# clogic.net
KiCad netlist of a schematic drawn in EAGLE
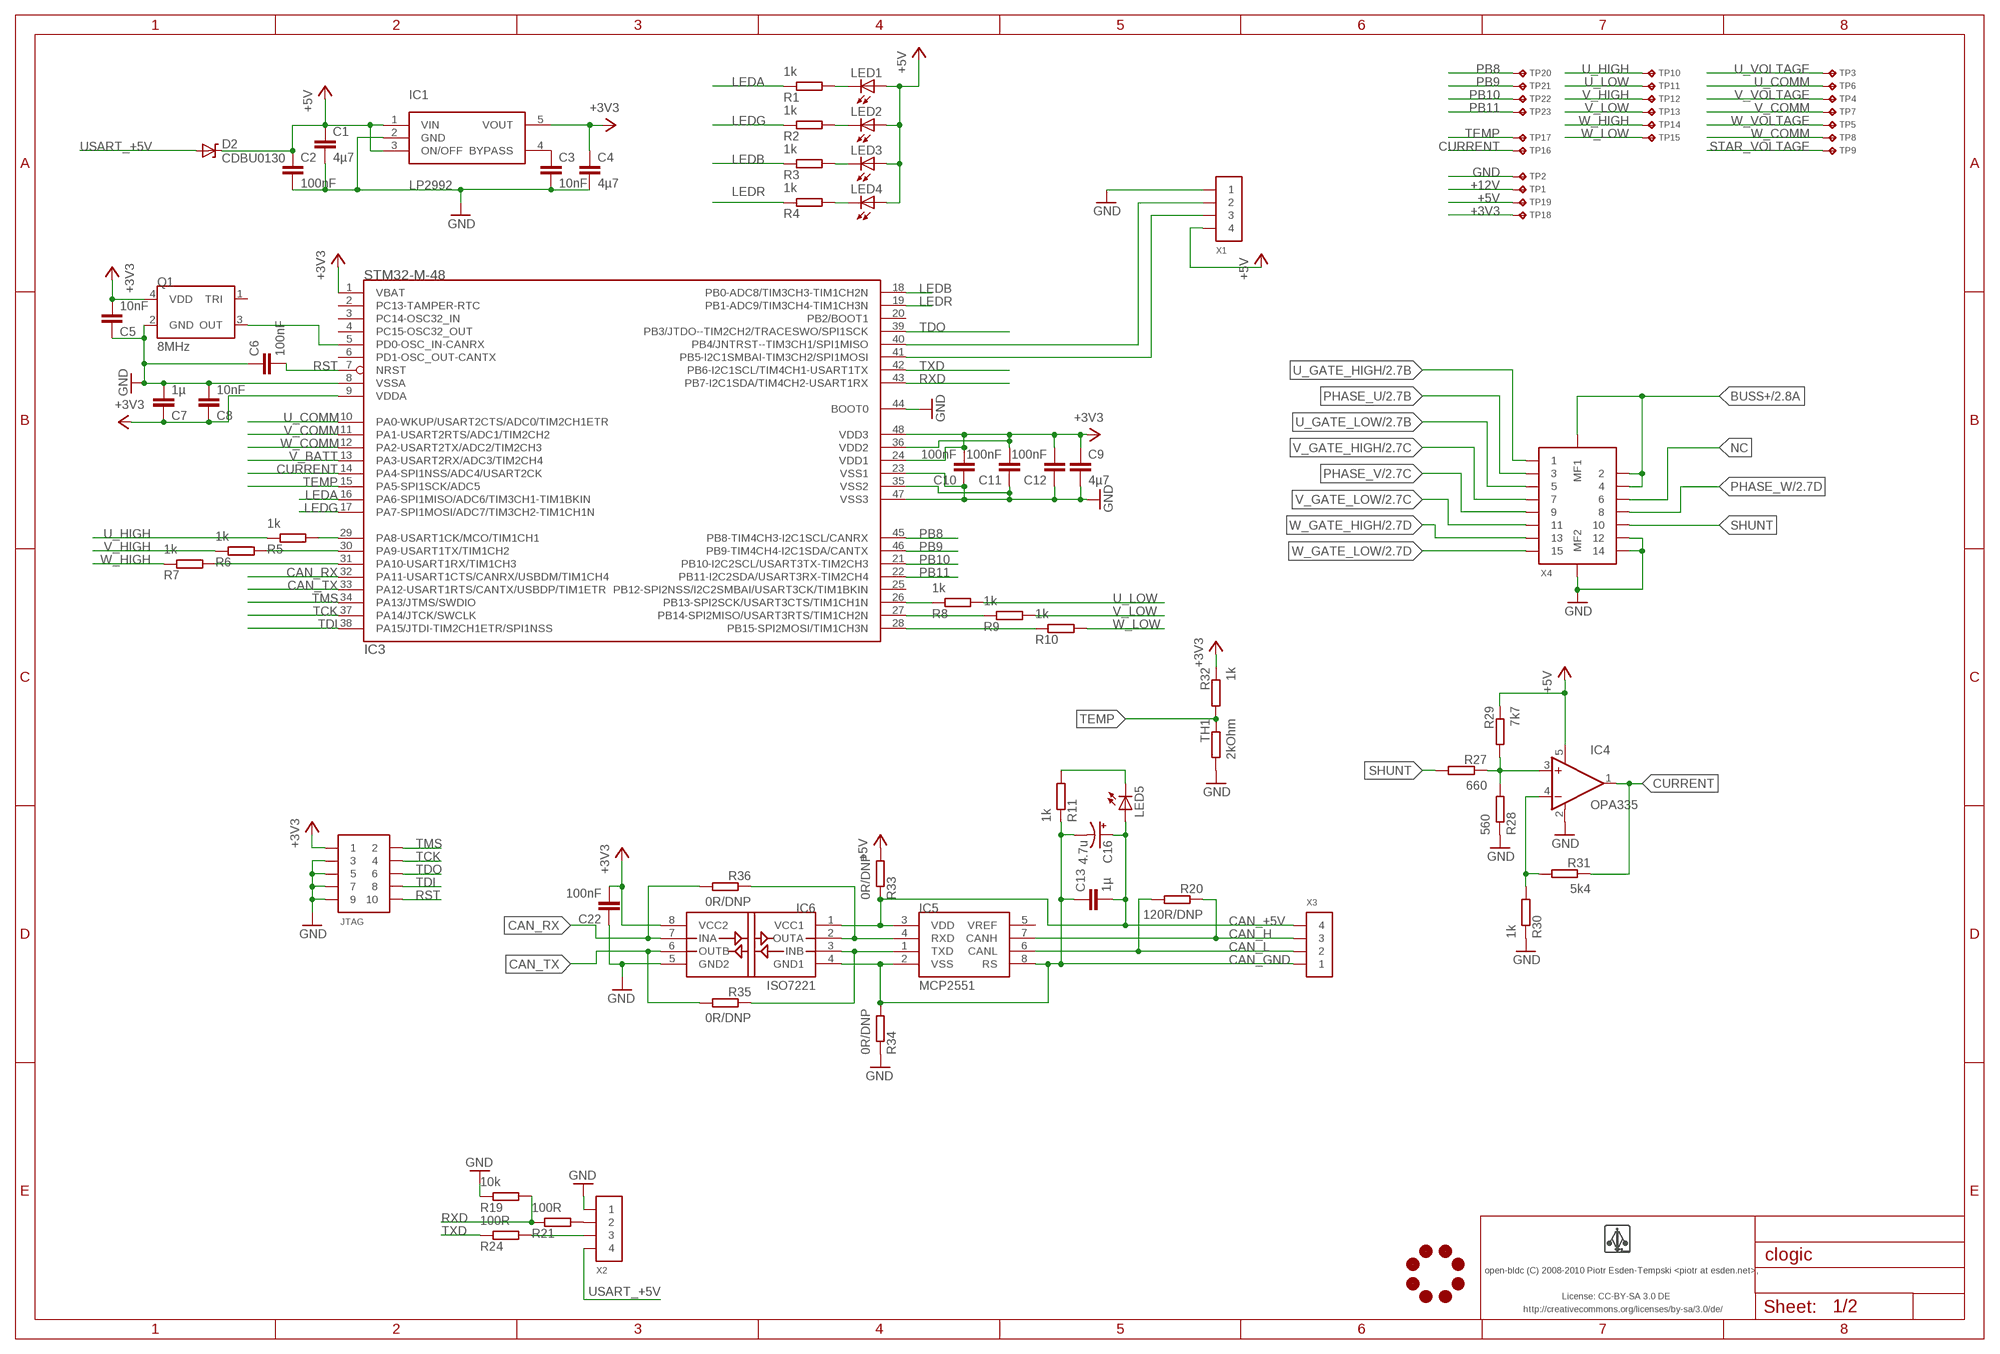
[diagram p0: schematic, sheet 1]
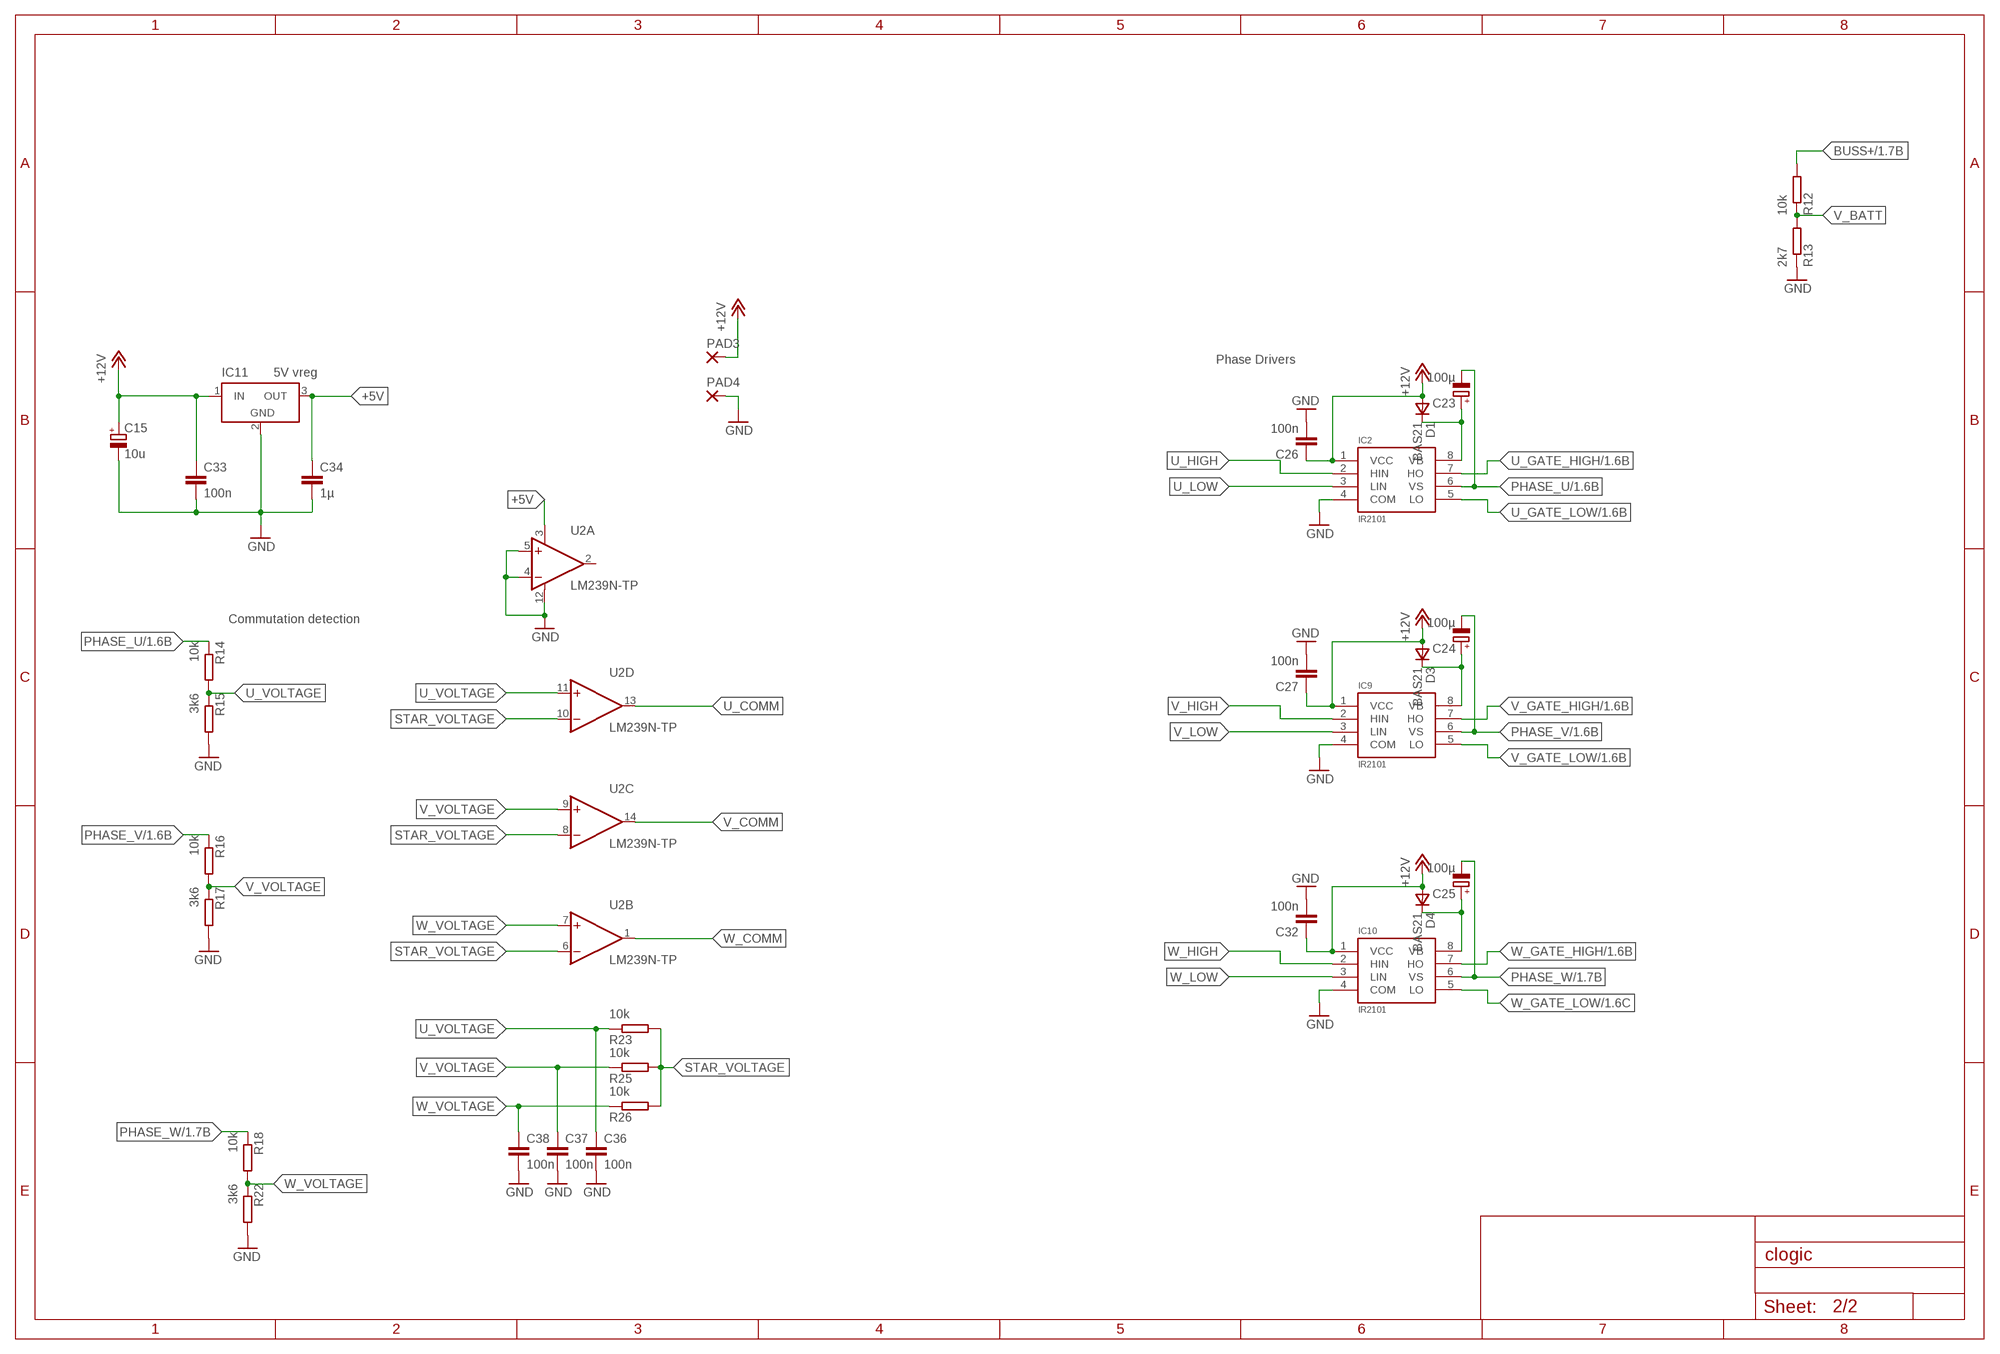
[diagram p1: schematic, sheet 2]

(export (version "E")
  (design (tool "Eeschema 10.0.6"))
  (components
    (comp (ref "C1")
      (value "4µ7")
      (footprint "eagle-import:0603-CAP")
      (libsource (lib "eagle-import") (part "CAPACITOR-0603"))
    )
    (comp (ref "C2")
      (value "100nF")
      (footprint "eagle-import:0603-CAP")
      (libsource (lib "eagle-import") (part "CAPACITOR-0603"))
    )
    (comp (ref "C3")
      (value "10nF")
      (footprint "eagle-import:0603-CAP")
      (libsource (lib "eagle-import") (part "CAPACITOR-0603"))
    )
    (comp (ref "C4")
      (value "4µ7")
      (footprint "eagle-import:0603-CAP")
      (libsource (lib "eagle-import") (part "CAPACITOR-0603"))
    )
    (comp (ref "C5")
      (value "10nF")
      (footprint "eagle-import:0603-CAP")
      (libsource (lib "eagle-import") (part "CAPACITOR-0603"))
    )
    (comp (ref "C6")
      (value "100nF")
      (footprint "eagle-import:0603-CAP")
      (libsource (lib "eagle-import") (part "CAPACITOR-0603"))
    )
    (comp (ref "C7")
      (value "1µ")
      (footprint "eagle-import:0603-CAP")
      (libsource (lib "eagle-import") (part "CAPACITOR-0603"))
    )
    (comp (ref "C8")
      (value "10nF")
      (footprint "eagle-import:0603-CAP")
      (libsource (lib "eagle-import") (part "CAPACITOR-0603"))
    )
    (comp (ref "C9")
      (value "4µ7")
      (footprint "eagle-import:0603-CAP")
      (libsource (lib "eagle-import") (part "CAPACITOR-0603"))
    )
    (comp (ref "C10")
      (value "100nF")
      (footprint "eagle-import:0603-CAP")
      (libsource (lib "eagle-import") (part "CAPACITOR-0603"))
    )
    (comp (ref "C11")
      (value "100nF")
      (footprint "eagle-import:0603-CAP")
      (libsource (lib "eagle-import") (part "CAPACITOR-0603"))
    )
    (comp (ref "C12")
      (value "100nF")
      (footprint "eagle-import:0603-CAP")
      (libsource (lib "eagle-import") (part "CAPACITOR-0603"))
    )
    (comp (ref "C13")
      (value "1µ")
      (footprint "eagle-import:0603-CAP")
      (libsource (lib "eagle-import") (part "CAPACITOR-0603"))
    )
    (comp (ref "C16")
      (value "4.7u")
      (footprint "eagle-import:CAP_0805TANT_F95")
      (libsource (lib "eagle-import") (part "CPOL-US"))
    )
    (comp (ref "C22")
      (value "100nF")
      (footprint "eagle-import:0603-CAP")
      (libsource (lib "eagle-import") (part "CAPACITOR-0603"))
    )
    (comp (ref "D2")
      (value "CDBU0130")
      (footprint "eagle-import:0603-LED")
      (libsource (lib "eagle-import") (part "DIODE-ZENER-0603"))
    )
    (comp (ref "IC1")
      (value "LP2992")
      (footprint "eagle-import:SOT23-5")
      (libsource (lib "eagle-import") (part "LP2992"))
    )
    (comp (ref "IC3")
      (value "STM32-M-48")
      (footprint "eagle-import:LQFP48")
      (libsource (lib "eagle-import") (part "STM32-M-48"))
    )
    (comp (ref "IC4")
      (value "OPA335")
      (footprint "eagle-import:SOT23-5")
      (libsource (lib "eagle-import") (part "OPA335"))
    )
    (comp (ref "IC5")
      (value "MCP2551")
      (footprint "eagle-import:SO8")
      (libsource (lib "eagle-import") (part "MCP2551"))
    )
    (comp (ref "IC6")
      (value "ISO7221")
      (footprint "eagle-import:SO8")
      (libsource (lib "eagle-import") (part "ISO7221"))
    )
    (comp (ref "JL1")
      (value "JOBY_LOGO-6MIL")
      (footprint "eagle-import:JOBY_LOGO_6MIL")
      (libsource (lib "eagle-import") (part "JOBY_LOGO-6MIL"))
    )
    (comp (ref "JTAG")
      (value "CONN_5-2-FTSH-V")
      (footprint "eagle-import:FTSH-105-DV")
      (libsource (lib "eagle-import") (part "CONN_5-2-FTSH-V"))
    )
    (comp (ref "LED1")
      (value "AMBER")
      (footprint "eagle-import:0603-LED")
      (libsource (lib "eagle-import") (part "LED-0603"))
    )
    (comp (ref "LED2")
      (value "GREEN")
      (footprint "eagle-import:0603-LED")
      (libsource (lib "eagle-import") (part "LED-0603"))
    )
    (comp (ref "LED3")
      (value "BLUE")
      (footprint "eagle-import:0603-LED")
      (libsource (lib "eagle-import") (part "LED-0603"))
    )
    (comp (ref "LED4")
      (value "RED")
      (footprint "eagle-import:0603-LED")
      (libsource (lib "eagle-import") (part "LED-0603"))
    )
    (comp (ref "LED5")
      (value "WHITE")
      (footprint "eagle-import:0603-LED")
      (libsource (lib "eagle-import") (part "LED-0603"))
    )
    (comp (ref "Q1")
      (value "8MHz")
      (footprint "eagle-import:ASE_OSCILLATOR")
      (libsource (lib "eagle-import") (part "ASE_ASCILLATOR"))
    )
    (comp (ref "R1")
      (value "1k")
      (footprint "eagle-import:0603-RES")
      (libsource (lib "eagle-import") (part "RESISTOR-0603"))
    )
    (comp (ref "R2")
      (value "1k")
      (footprint "eagle-import:0603-RES")
      (libsource (lib "eagle-import") (part "RESISTOR-0603"))
    )
    (comp (ref "R3")
      (value "1k")
      (footprint "eagle-import:0603-RES")
      (libsource (lib "eagle-import") (part "RESISTOR-0603"))
    )
    (comp (ref "R4")
      (value "1k")
      (footprint "eagle-import:0603-RES")
      (libsource (lib "eagle-import") (part "RESISTOR-0603"))
    )
    (comp (ref "R5")
      (value "1k")
      (footprint "eagle-import:0603-RES")
      (libsource (lib "eagle-import") (part "RESISTOR-0603"))
    )
    (comp (ref "R6")
      (value "1k")
      (footprint "eagle-import:0603-RES")
      (libsource (lib "eagle-import") (part "RESISTOR-0603"))
    )
    (comp (ref "R7")
      (value "1k")
      (footprint "eagle-import:0603-RES")
      (libsource (lib "eagle-import") (part "RESISTOR-0603"))
    )
    (comp (ref "R8")
      (value "1k")
      (footprint "eagle-import:0603-RES")
      (libsource (lib "eagle-import") (part "RESISTOR-0603"))
    )
    (comp (ref "R9")
      (value "1k")
      (footprint "eagle-import:0603-RES")
      (libsource (lib "eagle-import") (part "RESISTOR-0603"))
    )
    (comp (ref "R10")
      (value "1k")
      (footprint "eagle-import:0603-RES")
      (libsource (lib "eagle-import") (part "RESISTOR-0603"))
    )
    (comp (ref "R11")
      (value "1k")
      (footprint "eagle-import:0603-RES")
      (libsource (lib "eagle-import") (part "RESISTOR-0603"))
    )
    (comp (ref "R19")
      (value "10k")
      (footprint "eagle-import:0603-RES")
      (libsource (lib "eagle-import") (part "RESISTOR-0603"))
    )
    (comp (ref "R20")
      (value "120R/DNP")
      (footprint "eagle-import:0603-RES")
      (libsource (lib "eagle-import") (part "RESISTOR-0603"))
    )
    (comp (ref "R21")
      (value "100R")
      (footprint "eagle-import:0603-RES")
      (libsource (lib "eagle-import") (part "RESISTOR-0603"))
    )
    (comp (ref "R24")
      (value "100R")
      (footprint "eagle-import:0603-RES")
      (libsource (lib "eagle-import") (part "RESISTOR-0603"))
    )
    (comp (ref "R27")
      (value "660")
      (footprint "eagle-import:0603-RES")
      (libsource (lib "eagle-import") (part "RESISTOR-0603"))
    )
    (comp (ref "R28")
      (value "560")
      (footprint "eagle-import:0603-RES")
      (libsource (lib "eagle-import") (part "RESISTOR-0603"))
    )
    (comp (ref "R29")
      (value "7k7")
      (footprint "eagle-import:0603-RES")
      (libsource (lib "eagle-import") (part "RESISTOR-0603"))
    )
    (comp (ref "R30")
      (value "1k")
      (footprint "eagle-import:0603-RES")
      (libsource (lib "eagle-import") (part "RESISTOR-0603"))
    )
    (comp (ref "R31")
      (value "5k4")
      (footprint "eagle-import:0603-RES")
      (libsource (lib "eagle-import") (part "RESISTOR-0603"))
    )
    (comp (ref "R32")
      (value "1k")
      (footprint "eagle-import:0603-RES")
      (libsource (lib "eagle-import") (part "RESISTOR-0603"))
    )
    (comp (ref "R33")
      (value "0R/DNP")
      (footprint "eagle-import:0603-RES")
      (libsource (lib "eagle-import") (part "RESISTOR-0603"))
    )
    (comp (ref "R34")
      (value "0R/DNP")
      (footprint "eagle-import:0603-RES")
      (libsource (lib "eagle-import") (part "RESISTOR-0603"))
    )
    (comp (ref "R35")
      (value "0R/DNP")
      (footprint "eagle-import:0603-RES")
      (libsource (lib "eagle-import") (part "RESISTOR-0603"))
    )
    (comp (ref "R36")
      (value "0R/DNP")
      (footprint "eagle-import:0603-RES")
      (libsource (lib "eagle-import") (part "RESISTOR-0603"))
    )
    (comp (ref "TH1")
      (value "2kOhm")
      (footprint "eagle-import:0603-RES")
      (libsource (lib "eagle-import") (part "RESISTOR-0603"))
    )
    (comp (ref "TP1")
      (value "TP-09RSMD")
      (footprint "eagle-import:TP09R")
      (libsource (lib "eagle-import") (part "TP-09RSMD"))
    )
    (comp (ref "TP2")
      (value "TP-09RSMD")
      (footprint "eagle-import:TP09R")
      (libsource (lib "eagle-import") (part "TP-09RSMD"))
    )
    (comp (ref "TP3")
      (value "TP-09RSMD")
      (footprint "eagle-import:TP09R")
      (libsource (lib "eagle-import") (part "TP-09RSMD"))
    )
    (comp (ref "TP4")
      (value "TP-09RSMD")
      (footprint "eagle-import:TP09R")
      (libsource (lib "eagle-import") (part "TP-09RSMD"))
    )
    (comp (ref "TP5")
      (value "TP-09RSMD")
      (footprint "eagle-import:TP09R")
      (libsource (lib "eagle-import") (part "TP-09RSMD"))
    )
    (comp (ref "TP6")
      (value "TP-09RSMD")
      (footprint "eagle-import:TP09R")
      (libsource (lib "eagle-import") (part "TP-09RSMD"))
    )
    (comp (ref "TP7")
      (value "TP-09RSMD")
      (footprint "eagle-import:TP09R")
      (libsource (lib "eagle-import") (part "TP-09RSMD"))
    )
    (comp (ref "TP8")
      (value "TP-09RSMD")
      (footprint "eagle-import:TP09R")
      (libsource (lib "eagle-import") (part "TP-09RSMD"))
    )
    (comp (ref "TP9")
      (value "TP-09RSMD")
      (footprint "eagle-import:TP09R")
      (libsource (lib "eagle-import") (part "TP-09RSMD"))
    )
    (comp (ref "TP10")
      (value "TP-09RSMD")
      (footprint "eagle-import:TP09R")
      (libsource (lib "eagle-import") (part "TP-09RSMD"))
    )
    (comp (ref "TP11")
      (value "TP-09RSMD")
      (footprint "eagle-import:TP09R")
      (libsource (lib "eagle-import") (part "TP-09RSMD"))
    )
    (comp (ref "TP12")
      (value "TP-09RSMD")
      (footprint "eagle-import:TP09R")
      (libsource (lib "eagle-import") (part "TP-09RSMD"))
    )
    (comp (ref "TP13")
      (value "TP-09RSMD")
      (footprint "eagle-import:TP09R")
      (libsource (lib "eagle-import") (part "TP-09RSMD"))
    )
    (comp (ref "TP14")
      (value "TP-09RSMD")
      (footprint "eagle-import:TP09R")
      (libsource (lib "eagle-import") (part "TP-09RSMD"))
    )
    (comp (ref "TP15")
      (value "TP-09RSMD")
      (footprint "eagle-import:TP09R")
      (libsource (lib "eagle-import") (part "TP-09RSMD"))
    )
    (comp (ref "TP16")
      (value "TP-09RSMD")
      (footprint "eagle-import:TP09R")
      (libsource (lib "eagle-import") (part "TP-09RSMD"))
    )
    (comp (ref "TP17")
      (value "TP-09RSMD")
      (footprint "eagle-import:TP09R")
      (libsource (lib "eagle-import") (part "TP-09RSMD"))
    )
    (comp (ref "TP18")
      (value "TP-09RSMD")
      (footprint "eagle-import:TP09R")
      (libsource (lib "eagle-import") (part "TP-09RSMD"))
    )
    (comp (ref "TP19")
      (value "TP-09RSMD")
      (footprint "eagle-import:TP09R")
      (libsource (lib "eagle-import") (part "TP-09RSMD"))
    )
    (comp (ref "TP20")
      (value "TP-09RSMD")
      (footprint "eagle-import:TP09R")
      (libsource (lib "eagle-import") (part "TP-09RSMD"))
    )
    (comp (ref "TP21")
      (value "TP-09RSMD")
      (footprint "eagle-import:TP09R")
      (libsource (lib "eagle-import") (part "TP-09RSMD"))
    )
    (comp (ref "TP22")
      (value "TP-09RSMD")
      (footprint "eagle-import:TP09R")
      (libsource (lib "eagle-import") (part "TP-09RSMD"))
    )
    (comp (ref "TP23")
      (value "TP-09RSMD")
      (footprint "eagle-import:TP09R")
      (libsource (lib "eagle-import") (part "TP-09RSMD"))
    )
    (comp (ref "U$1")
      (value "LOGO")
      (footprint "eagle-import:LOGO")
      (libsource (lib "eagle-import") (part "LOGO-NORM"))
    )
    (comp (ref "X1")
      (value "CONN_4-1-53261")
      (footprint "eagle-import:PB-53261-04")
      (libsource (lib "eagle-import") (part "CONN_4-1-53261"))
    )
    (comp (ref "X2")
      (value "CONN_4-1-53261")
      (footprint "eagle-import:PB-53261-04")
      (libsource (lib "eagle-import") (part "CONN_4-1-53261"))
    )
    (comp (ref "X3")
      (value "CONN_4-1-53261")
      (footprint "eagle-import:PB-53261-04")
      (libsource (lib "eagle-import") (part "CONN_4-1-53261"))
    )
    (comp (ref "X4")
      (value "CONN_15-2-2MT-DF9")
      (footprint "eagle-import:DF9-15")
      (libsource (lib "eagle-import") (part "CONN_15-2-2MT-DF9"))
    )
    (comp (ref "C15")
      (value "10u")
      (footprint "eagle-import:3528_B")
      (libsource (lib "eagle-import") (part "CAPACITOR-POLB"))
    )
    (comp (ref "C23")
      (value "100µ")
      (footprint "eagle-import:0805-POL-CAP")
      (libsource (lib "eagle-import") (part "CAPACITOR-POL-0805"))
    )
    (comp (ref "C24")
      (value "100µ")
      (footprint "eagle-import:0805-POL-CAP")
      (libsource (lib "eagle-import") (part "CAPACITOR-POL-0805"))
    )
    (comp (ref "C25")
      (value "100µ")
      (footprint "eagle-import:0805-POL-CAP")
      (libsource (lib "eagle-import") (part "CAPACITOR-POL-0805"))
    )
    (comp (ref "C26")
      (value "100n")
      (footprint "eagle-import:0603-CAP")
      (libsource (lib "eagle-import") (part "CAPACITOR-0603"))
    )
    (comp (ref "C27")
      (value "100n")
      (footprint "eagle-import:0603-CAP")
      (libsource (lib "eagle-import") (part "CAPACITOR-0603"))
    )
    (comp (ref "C32")
      (value "100n")
      (footprint "eagle-import:0603-CAP")
      (libsource (lib "eagle-import") (part "CAPACITOR-0603"))
    )
    (comp (ref "C33")
      (value "100n")
      (footprint "eagle-import:0603-CAP")
      (libsource (lib "eagle-import") (part "CAPACITOR-0603"))
    )
    (comp (ref "C34")
      (value "1µ")
      (footprint "eagle-import:0603-CAP")
      (libsource (lib "eagle-import") (part "CAPACITOR-0603"))
    )
    (comp (ref "C36")
      (value "100n")
      (footprint "eagle-import:0603-CAP")
      (libsource (lib "eagle-import") (part "CAPACITOR-0603"))
    )
    (comp (ref "C37")
      (value "100n")
      (footprint "eagle-import:0603-CAP")
      (libsource (lib "eagle-import") (part "CAPACITOR-0603"))
    )
    (comp (ref "C38")
      (value "100n")
      (footprint "eagle-import:0603-CAP")
      (libsource (lib "eagle-import") (part "CAPACITOR-0603"))
    )
    (comp (ref "D1")
      (value "BAS21")
      (footprint "eagle-import:SOT-23")
      (libsource (lib "eagle-import") (part "VAR2SOT23"))
    )
    (comp (ref "D3")
      (value "BAS21")
      (footprint "eagle-import:SOT-23")
      (libsource (lib "eagle-import") (part "VAR2SOT23"))
    )
    (comp (ref "D4")
      (value "BAS21")
      (footprint "eagle-import:SOT-23")
      (libsource (lib "eagle-import") (part "VAR2SOT23"))
    )
    (comp (ref "IC2")
      (value "IR2101")
      (footprint "eagle-import:SO-8")
      (libsource (lib "eagle-import") (part "IR2101"))
    )
    (comp (ref "IC9")
      (value "IR2101")
      (footprint "eagle-import:SO-8")
      (libsource (lib "eagle-import") (part "IR2101"))
    )
    (comp (ref "IC10")
      (value "IR2101")
      (footprint "eagle-import:SO-8")
      (libsource (lib "eagle-import") (part "IR2101"))
    )
    (comp (ref "IC11")
      (value "5V vreg")
      (footprint "eagle-import:SOT223")
      (libsource (lib "eagle-import") (part "LT1129CST5"))
    )
    (comp (ref "PAD3")
      (value "SMD5")
      (footprint "eagle-import:SMD2,54-5,08")
      (libsource (lib "eagle-import") (part "SMD5"))
    )
    (comp (ref "PAD4")
      (value "SMD5")
      (footprint "eagle-import:SMD2,54-5,08")
      (libsource (lib "eagle-import") (part "SMD5"))
    )
    (comp (ref "R12")
      (value "10k")
      (footprint "eagle-import:0603-RES")
      (libsource (lib "eagle-import") (part "RESISTOR-0603"))
    )
    (comp (ref "R13")
      (value "2k7")
      (footprint "eagle-import:0603-RES")
      (libsource (lib "eagle-import") (part "RESISTOR-0603"))
    )
    (comp (ref "R14")
      (value "10k")
      (footprint "eagle-import:0603-RES")
      (libsource (lib "eagle-import") (part "RESISTOR-0603"))
    )
    (comp (ref "R15")
      (value "3k6")
      (footprint "eagle-import:0603-RES")
      (libsource (lib "eagle-import") (part "RESISTOR-0603"))
    )
    (comp (ref "R16")
      (value "10k")
      (footprint "eagle-import:0603-RES")
      (libsource (lib "eagle-import") (part "RESISTOR-0603"))
    )
    (comp (ref "R17")
      (value "3k6")
      (footprint "eagle-import:0603-RES")
      (libsource (lib "eagle-import") (part "RESISTOR-0603"))
    )
    (comp (ref "R18")
      (value "10k")
      (footprint "eagle-import:0603-RES")
      (libsource (lib "eagle-import") (part "RESISTOR-0603"))
    )
    (comp (ref "R22")
      (value "3k6")
      (footprint "eagle-import:0603-RES")
      (libsource (lib "eagle-import") (part "RESISTOR-0603"))
    )
    (comp (ref "R23")
      (value "10k")
      (footprint "eagle-import:0603-RES")
      (libsource (lib "eagle-import") (part "RESISTOR-0603"))
    )
    (comp (ref "R25")
      (value "10k")
      (footprint "eagle-import:0603-RES")
      (libsource (lib "eagle-import") (part "RESISTOR-0603"))
    )
    (comp (ref "R26")
      (value "10k")
      (footprint "eagle-import:0603-RES")
      (libsource (lib "eagle-import") (part "RESISTOR-0603"))
    )
    (comp (ref "U2")
      (value "LM239N-TP")
      (footprint "eagle-import:TSSOP_14")
      (libsource (lib "eagle-import") (part "LM239N-TP"))
    )
  )
  (nets
    (net (code "1") (name "+3V3") (class "Default")
      (node (ref "C10") (pin "P$2") (pinfunction "2_P$2") (pintype "passive"))
      (node (ref "C11") (pin "P$2") (pinfunction "2_P$2") (pintype "passive"))
      (node (ref "C12") (pin "P$2") (pinfunction "2_P$2") (pintype "passive"))
      (node (ref "C22") (pin "P$2") (pinfunction "2_P$2") (pintype "passive"))
      (node (ref "C4") (pin "P$1") (pinfunction "1_P$1") (pintype "passive"))
      (node (ref "C5") (pin "P$2") (pinfunction "2_P$2") (pintype "passive"))
      (node (ref "C7") (pin "P$1") (pinfunction "1_P$1") (pintype "passive"))
      (node (ref "C8") (pin "P$1") (pinfunction "1_P$1") (pintype "passive"))
      (node (ref "C9") (pin "P$1") (pinfunction "1_P$1") (pintype "passive"))
      (node (ref "IC1") (pin "5") (pinfunction "VOUT_5") (pintype "bidirectional"))
      (node (ref "IC3") (pin "1") (pinfunction "VBAT_1") (pintype "power_in"))
      (node (ref "IC3") (pin "24") (pinfunction "VDD1_24") (pintype "power_in"))
      (node (ref "IC3") (pin "36") (pinfunction "VDD2_36") (pintype "power_in"))
      (node (ref "IC3") (pin "48") (pinfunction "VDD3_48") (pintype "power_in"))
      (node (ref "IC3") (pin "9") (pinfunction "VDDA_9") (pintype "power_in"))
      (node (ref "IC6") (pin "8") (pinfunction "VCC2_8") (pintype "bidirectional"))
      (node (ref "JTAG") (pin "1") (pinfunction "1_1") (pintype "bidirectional"))
      (node (ref "Q1") (pin "4") (pinfunction "VDD_4") (pintype "power_in"))
      (node (ref "R32") (pin "P$1") (pinfunction "1_P$1") (pintype "passive"))
      (node (ref "TP18") (pin "P$1") (pinfunction "1_P$1") (pintype "bidirectional"))
    )
    (net (code "2") (name "+5V") (class "Default")
      (node (ref "C1") (pin "P$1") (pinfunction "1_P$1") (pintype "passive"))
      (node (ref "C2") (pin "P$1") (pinfunction "1_P$1") (pintype "passive"))
      (node (ref "C34") (pin "P$1") (pinfunction "1_P$1") (pintype "passive"))
      (node (ref "D2") (pin "C") (pinfunction "C_C") (pintype "passive"))
      (node (ref "IC1") (pin "1") (pinfunction "VIN_1") (pintype "bidirectional"))
      (node (ref "IC1") (pin "3") (pinfunction "ON/OFF_3") (pintype "bidirectional"))
      (node (ref "IC11") (pin "3") (pinfunction "OUT_3") (pintype "power_in"))
      (node (ref "IC4") (pin "5") (pinfunction "V+_5") (pintype "power_in"))
      (node (ref "LED1") (pin "A") (pinfunction "A_A") (pintype "passive"))
      (node (ref "LED2") (pin "A") (pinfunction "A_A") (pintype "passive"))
      (node (ref "LED3") (pin "A") (pinfunction "A_A") (pintype "passive"))
      (node (ref "LED4") (pin "A") (pinfunction "A_A") (pintype "passive"))
      (node (ref "R29") (pin "P$1") (pinfunction "1_P$1") (pintype "passive"))
      (node (ref "R33") (pin "P$2") (pinfunction "2_P$2") (pintype "passive"))
      (node (ref "TP19") (pin "P$1") (pinfunction "1_P$1") (pintype "bidirectional"))
      (node (ref "U2") (pin "3") (pinfunction "V+_3") (pintype "power_in"))
      (node (ref "X1") (pin "4") (pinfunction "4_4") (pintype "bidirectional"))
    )
    (net (code "3") (name "+12V") (class "Default")
      (node (ref "C15") (pin "+") (pinfunction "+_+") (pintype "passive"))
      (node (ref "C26") (pin "P$1") (pinfunction "1_P$1") (pintype "passive"))
      (node (ref "C27") (pin "P$1") (pinfunction "1_P$1") (pintype "passive"))
      (node (ref "C32") (pin "P$1") (pinfunction "1_P$1") (pintype "passive"))
      (node (ref "C33") (pin "P$1") (pinfunction "1_P$1") (pintype "passive"))
      (node (ref "D1") (pin "3") (pinfunction "A_3") (pintype "passive"))
      (node (ref "D3") (pin "3") (pinfunction "A_3") (pintype "passive"))
      (node (ref "D4") (pin "3") (pinfunction "A_3") (pintype "passive"))
      (node (ref "IC10") (pin "1") (pinfunction "VCC_1") (pintype "bidirectional"))
      (node (ref "IC11") (pin "1") (pinfunction "IN_1") (pintype "input"))
      (node (ref "IC2") (pin "1") (pinfunction "VCC_1") (pintype "bidirectional"))
      (node (ref "IC9") (pin "1") (pinfunction "VCC_1") (pintype "bidirectional"))
      (node (ref "PAD3") (pin "1") (pinfunction "P_1") (pintype "passive"))
      (node (ref "TP1") (pin "P$1") (pinfunction "1_P$1") (pintype "bidirectional"))
    )
    (net (code "4") (name "BUSS+") (class "Default")
      (node (ref "R12") (pin "P$2") (pinfunction "2_P$2") (pintype "passive"))
      (node (ref "X4") (pin "2") (pinfunction "2_2") (pintype "bidirectional"))
      (node (ref "X4") (pin "4") (pinfunction "4_4") (pintype "bidirectional"))
      (node (ref "X4") (pin "MF1") (pinfunction "MF1_MF1") (pintype "bidirectional"))
    )
    (net (code "5") (name "CAN_+5V") (class "Default")
      (node (ref "C13") (pin "P$2") (pinfunction "2_P$2") (pintype "passive"))
      (node (ref "C16") (pin "P$1") (pinfunction "+_P$1") (pintype "passive"))
      (node (ref "IC5") (pin "3") (pinfunction "VDD_3") (pintype "bidirectional"))
      (node (ref "IC6") (pin "1") (pinfunction "VCC1_1") (pintype "bidirectional"))
      (node (ref "LED5") (pin "A") (pinfunction "A_A") (pintype "passive"))
      (node (ref "R33") (pin "P$1") (pinfunction "1_P$1") (pintype "passive"))
      (node (ref "X3") (pin "4") (pinfunction "4_4") (pintype "bidirectional"))
    )
    (net (code "6") (name "CAN_GND") (class "Default")
      (node (ref "C13") (pin "P$1") (pinfunction "1_P$1") (pintype "passive"))
      (node (ref "C16") (pin "P$2") (pinfunction "-_P$2") (pintype "passive"))
      (node (ref "IC5") (pin "2") (pinfunction "VSS_2") (pintype "bidirectional"))
      (node (ref "IC5") (pin "8") (pinfunction "RS_8") (pintype "bidirectional"))
      (node (ref "IC6") (pin "4") (pinfunction "GND1_4") (pintype "bidirectional"))
      (node (ref "R11") (pin "P$1") (pinfunction "1_P$1") (pintype "passive"))
      (node (ref "R34") (pin "P$2") (pinfunction "2_P$2") (pintype "passive"))
      (node (ref "X3") (pin "1") (pinfunction "1_1") (pintype "bidirectional"))
    )
    (net (code "7") (name "CAN_H") (class "Default")
      (node (ref "IC5") (pin "7") (pinfunction "CANH_7") (pintype "bidirectional"))
      (node (ref "R20") (pin "P$1") (pinfunction "1_P$1") (pintype "passive"))
      (node (ref "X3") (pin "3") (pinfunction "3_3") (pintype "bidirectional"))
    )
    (net (code "8") (name "CAN_L") (class "Default")
      (node (ref "IC5") (pin "6") (pinfunction "CANL_6") (pintype "bidirectional"))
      (node (ref "R20") (pin "P$2") (pinfunction "2_P$2") (pintype "passive"))
      (node (ref "X3") (pin "2") (pinfunction "2_2") (pintype "bidirectional"))
    )
    (net (code "9") (name "CAN_RX") (class "Default")
      (node (ref "IC3") (pin "32") (pinfunction "PA11-USART1CTS/CANRX/USBDM/TIM1CH4_32") (pintype "bidirectional"))
      (node (ref "IC6") (pin "7") (pinfunction "INA_7") (pintype "bidirectional"))
      (node (ref "R36") (pin "P$2") (pinfunction "2_P$2") (pintype "passive"))
    )
    (net (code "10") (name "CAN_TX") (class "Default")
      (node (ref "IC3") (pin "33") (pinfunction "PA12-USART1RTS/CANTX/USBDP/TIM1ETR_33") (pintype "bidirectional"))
      (node (ref "IC6") (pin "6") (pinfunction "OUTB_6") (pintype "bidirectional"))
      (node (ref "R35") (pin "P$2") (pinfunction "2_P$2") (pintype "passive"))
    )
    (net (code "11") (name "CURRENT") (class "Default")
      (node (ref "IC3") (pin "14") (pinfunction "PA4-SPI1NSS/ADC4/USART2CK_14") (pintype "bidirectional"))
      (node (ref "IC4") (pin "1") (pinfunction "OUT_1") (pintype "output"))
      (node (ref "R31") (pin "P$1") (pinfunction "1_P$1") (pintype "passive"))
      (node (ref "TP16") (pin "P$1") (pinfunction "1_P$1") (pintype "bidirectional"))
    )
    (net (code "12") (name "GND") (class "Default")
      (node (ref "C1") (pin "P$2") (pinfunction "2_P$2") (pintype "passive"))
      (node (ref "C10") (pin "P$1") (pinfunction "1_P$1") (pintype "passive"))
      (node (ref "C11") (pin "P$1") (pinfunction "1_P$1") (pintype "passive"))
      (node (ref "C12") (pin "P$1") (pinfunction "1_P$1") (pintype "passive"))
      (node (ref "C15") (pin "-") (pinfunction "-_-") (pintype "passive"))
      (node (ref "C2") (pin "P$2") (pinfunction "2_P$2") (pintype "passive"))
      (node (ref "C22") (pin "P$1") (pinfunction "1_P$1") (pintype "passive"))
      (node (ref "C26") (pin "P$2") (pinfunction "2_P$2") (pintype "passive"))
      (node (ref "C27") (pin "P$2") (pinfunction "2_P$2") (pintype "passive"))
      (node (ref "C3") (pin "P$2") (pinfunction "2_P$2") (pintype "passive"))
      (node (ref "C32") (pin "P$2") (pinfunction "2_P$2") (pintype "passive"))
      (node (ref "C33") (pin "P$2") (pinfunction "2_P$2") (pintype "passive"))
      (node (ref "C34") (pin "P$2") (pinfunction "2_P$2") (pintype "passive"))
      (node (ref "C36") (pin "P$2") (pinfunction "2_P$2") (pintype "passive"))
      (node (ref "C37") (pin "P$2") (pinfunction "2_P$2") (pintype "passive"))
      (node (ref "C38") (pin "P$2") (pinfunction "2_P$2") (pintype "passive"))
      (node (ref "C4") (pin "P$2") (pinfunction "2_P$2") (pintype "passive"))
      (node (ref "C5") (pin "P$1") (pinfunction "1_P$1") (pintype "passive"))
      (node (ref "C6") (pin "P$1") (pinfunction "1_P$1") (pintype "passive"))
      (node (ref "C7") (pin "P$2") (pinfunction "2_P$2") (pintype "passive"))
      (node (ref "C8") (pin "P$2") (pinfunction "2_P$2") (pintype "passive"))
      (node (ref "C9") (pin "P$2") (pinfunction "2_P$2") (pintype "passive"))
      (node (ref "IC1") (pin "2") (pinfunction "GND_2") (pintype "bidirectional"))
      (node (ref "IC10") (pin "4") (pinfunction "COM_4") (pintype "bidirectional"))
      (node (ref "IC11") (pin "2") (pinfunction "GND_2") (pintype "power_in"))
      (node (ref "IC2") (pin "4") (pinfunction "COM_4") (pintype "bidirectional"))
      (node (ref "IC3") (pin "23") (pinfunction "VSS1_23") (pintype "power_in"))
      (node (ref "IC3") (pin "35") (pinfunction "VSS2_35") (pintype "power_in"))
      (node (ref "IC3") (pin "44") (pinfunction "BOOT0_44") (pintype "input"))
      (node (ref "IC3") (pin "47") (pinfunction "VSS3_47") (pintype "power_in"))
      (node (ref "IC3") (pin "8") (pinfunction "VSSA_8") (pintype "power_in"))
      (node (ref "IC4") (pin "2") (pinfunction "V-_2") (pintype "power_in"))
      (node (ref "IC6") (pin "5") (pinfunction "GND2_5") (pintype "bidirectional"))
      (node (ref "IC9") (pin "4") (pinfunction "COM_4") (pintype "bidirectional"))
      (node (ref "JTAG") (pin "3") (pinfunction "3_3") (pintype "bidirectional"))
      (node (ref "JTAG") (pin "5") (pinfunction "5_5") (pintype "bidirectional"))
      (node (ref "JTAG") (pin "7") (pinfunction "7_7") (pintype "bidirectional"))
      (node (ref "JTAG") (pin "9") (pinfunction "9_9") (pintype "bidirectional"))
      (node (ref "PAD4") (pin "1") (pinfunction "P_1") (pintype "passive"))
      (node (ref "Q1") (pin "2") (pinfunction "GND_2") (pintype "power_in"))
      (node (ref "R13") (pin "P$1") (pinfunction "1_P$1") (pintype "passive"))
      (node (ref "R15") (pin "P$2") (pinfunction "2_P$2") (pintype "passive"))
      (node (ref "R17") (pin "P$2") (pinfunction "2_P$2") (pintype "passive"))
      (node (ref "R19") (pin "P$1") (pinfunction "1_P$1") (pintype "passive"))
      (node (ref "R22") (pin "P$2") (pinfunction "2_P$2") (pintype "passive"))
      (node (ref "R28") (pin "P$1") (pinfunction "1_P$1") (pintype "passive"))
      (node (ref "R30") (pin "P$1") (pinfunction "1_P$1") (pintype "passive"))
      (node (ref "R34") (pin "P$1") (pinfunction "1_P$1") (pintype "passive"))
      (node (ref "TH1") (pin "P$2") (pinfunction "2_P$2") (pintype "passive"))
      (node (ref "TP2") (pin "P$1") (pinfunction "1_P$1") (pintype "bidirectional"))
      (node (ref "U2") (pin "12") (pinfunction "V-_12") (pintype "power_in"))
      (node (ref "U2") (pin "4") (pinfunction "-IN_4") (pintype "input"))
      (node (ref "U2") (pin "5") (pinfunction "+IN_5") (pintype "input"))
      (node (ref "X1") (pin "1") (pinfunction "1_1") (pintype "bidirectional"))
      (node (ref "X2") (pin "1") (pinfunction "1_1") (pintype "bidirectional"))
      (node (ref "X4") (pin "12") (pinfunction "12_12") (pintype "bidirectional"))
      (node (ref "X4") (pin "14") (pinfunction "14_14") (pintype "bidirectional"))
      (node (ref "X4") (pin "MF2") (pinfunction "MF2_MF2") (pintype "bidirectional"))
    )
    (net (code "13") (name "LEDA") (class "Default")
      (node (ref "IC3") (pin "16") (pinfunction "PA6-SPI1MISO/ADC6/TIM3CH1-TIM1BKIN_16") (pintype "bidirectional"))
      (node (ref "R1") (pin "P$1") (pinfunction "1_P$1") (pintype "passive"))
    )
    (net (code "14") (name "LEDB") (class "Default")
      (node (ref "IC3") (pin "18") (pinfunction "PB0-ADC8/TIM3CH3-TIM1CH2N_18") (pintype "bidirectional"))
      (node (ref "R3") (pin "P$1") (pinfunction "1_P$1") (pintype "passive"))
    )
    (net (code "15") (name "LEDG") (class "Default")
      (node (ref "IC3") (pin "17") (pinfunction "PA7-SPI1MOSI/ADC7/TIM3CH2-TIM1CH1N_17") (pintype "bidirectional"))
      (node (ref "R2") (pin "P$1") (pinfunction "1_P$1") (pintype "passive"))
    )
    (net (code "16") (name "LEDR") (class "Default")
      (node (ref "IC3") (pin "19") (pinfunction "PB1-ADC9/TIM3CH4-TIM1CH3N_19") (pintype "bidirectional"))
      (node (ref "R4") (pin "P$1") (pinfunction "1_P$1") (pintype "passive"))
    )
    (net (code "17") (name "NC") (class "Default")
      (node (ref "X4") (pin "6") (pinfunction "6_6") (pintype "bidirectional"))
    )
    (net (code "18") (name "Net-(C3-1)") (class "Default")
      (node (ref "C3") (pin "P$1") (pinfunction "1_P$1") (pintype "passive"))
      (node (ref "IC1") (pin "4") (pinfunction "BYPASS_4") (pintype "bidirectional"))
    )
    (net (code "19") (name "Net-(D1-C)") (class "Default")
      (node (ref "C23") (pin "+") (pinfunction "+_+") (pintype "passive"))
      (node (ref "D1") (pin "1") (pinfunction "C_1") (pintype "passive"))
      (node (ref "IC2") (pin "8") (pinfunction "VB_8") (pintype "bidirectional"))
    )
    (net (code "20") (name "Net-(D3-C)") (class "Default")
      (node (ref "C24") (pin "+") (pinfunction "+_+") (pintype "passive"))
      (node (ref "D3") (pin "1") (pinfunction "C_1") (pintype "passive"))
      (node (ref "IC9") (pin "8") (pinfunction "VB_8") (pintype "bidirectional"))
    )
    (net (code "21") (name "Net-(D4-C)") (class "Default")
      (node (ref "C25") (pin "+") (pinfunction "+_+") (pintype "passive"))
      (node (ref "D4") (pin "1") (pinfunction "C_1") (pintype "passive"))
      (node (ref "IC10") (pin "8") (pinfunction "VB_8") (pintype "bidirectional"))
    )
    (net (code "22") (name "Net-(IC3-PA8-USART1CK{slash}MCO{slash}TIM1CH1)") (class "Default")
      (node (ref "IC3") (pin "29") (pinfunction "PA8-USART1CK/MCO/TIM1CH1_29") (pintype "bidirectional"))
      (node (ref "R5") (pin "P$2") (pinfunction "2_P$2") (pintype "passive"))
    )
    (net (code "23") (name "Net-(IC3-PA9-USART1TX{slash}TIM1CH2)") (class "Default")
      (node (ref "IC3") (pin "30") (pinfunction "PA9-USART1TX/TIM1CH2_30") (pintype "bidirectional"))
      (node (ref "R6") (pin "P$2") (pinfunction "2_P$2") (pintype "passive"))
    )
    (net (code "24") (name "Net-(IC3-PA10-USART1RX{slash}TIM1CH3)") (class "Default")
      (node (ref "IC3") (pin "31") (pinfunction "PA10-USART1RX/TIM1CH3_31") (pintype "bidirectional"))
      (node (ref "R7") (pin "P$2") (pinfunction "2_P$2") (pintype "passive"))
    )
    (net (code "25") (name "Net-(IC3-PB4{slash}JNTRST--TIM3CH1{slash}SPI1MISO)") (class "Default")
      (node (ref "IC3") (pin "40") (pinfunction "PB4/JNTRST--TIM3CH1/SPI1MISO_40") (pintype "bidirectional"))
      (node (ref "X1") (pin "2") (pinfunction "2_2") (pintype "bidirectional"))
    )
    (net (code "26") (name "Net-(IC3-PB5-I2C1SMBAI-TIM3CH2{slash}SPI1MOSI)") (class "Default")
      (node (ref "IC3") (pin "41") (pinfunction "PB5-I2C1SMBAI-TIM3CH2/SPI1MOSI_41") (pintype "bidirectional"))
      (node (ref "X1") (pin "3") (pinfunction "3_3") (pintype "bidirectional"))
    )
    (net (code "27") (name "Net-(IC3-PB13-SPI2SCK{slash}USART3CTS{slash}TIM1CH1N)") (class "Default")
      (node (ref "IC3") (pin "26") (pinfunction "PB13-SPI2SCK/USART3CTS/TIM1CH1N_26") (pintype "bidirectional"))
      (node (ref "R8") (pin "P$1") (pinfunction "1_P$1") (pintype "passive"))
    )
    (net (code "28") (name "Net-(IC3-PB14-SPI2MISO{slash}USART3RTS{slash}TIM1CH2N)") (class "Default")
      (node (ref "IC3") (pin "27") (pinfunction "PB14-SPI2MISO/USART3RTS/TIM1CH2N_27") (pintype "bidirectional"))
      (node (ref "R9") (pin "P$1") (pinfunction "1_P$1") (pintype "passive"))
    )
    (net (code "29") (name "Net-(IC3-PB15-SPI2MOSI{slash}TIM1CH3N)") (class "Default")
      (node (ref "IC3") (pin "28") (pinfunction "PB15-SPI2MOSI/TIM1CH3N_28") (pintype "bidirectional"))
      (node (ref "R10") (pin "P$1") (pinfunction "1_P$1") (pintype "passive"))
    )
    (net (code "30") (name "Net-(IC3-PD0-OSC_IN-CANRX)") (class "Default")
      (node (ref "IC3") (pin "5") (pinfunction "PD0-OSC_IN-CANRX_5") (pintype "input"))
      (node (ref "Q1") (pin "3") (pinfunction "OUT_3") (pintype "output"))
    )
    (net (code "31") (name "Net-(IC4-+IN)") (class "Default")
      (node (ref "IC4") (pin "3") (pinfunction "+IN_3") (pintype "input"))
      (node (ref "R27") (pin "P$1") (pinfunction "1_P$1") (pintype "passive"))
      (node (ref "R28") (pin "P$2") (pinfunction "2_P$2") (pintype "passive"))
      (node (ref "R29") (pin "P$2") (pinfunction "2_P$2") (pintype "passive"))
    )
    (net (code "32") (name "Net-(IC4--IN)") (class "Default")
      (node (ref "IC4") (pin "4") (pinfunction "-IN_4") (pintype "input"))
      (node (ref "R30") (pin "P$2") (pinfunction "2_P$2") (pintype "passive"))
      (node (ref "R31") (pin "P$2") (pinfunction "2_P$2") (pintype "passive"))
    )
    (net (code "33") (name "Net-(IC5-RXD)") (class "Default")
      (node (ref "IC5") (pin "4") (pinfunction "RXD_4") (pintype "bidirectional"))
      (node (ref "IC6") (pin "2") (pinfunction "OUTA_2") (pintype "bidirectional"))
      (node (ref "R36") (pin "P$1") (pinfunction "1_P$1") (pintype "passive"))
    )
    (net (code "34") (name "Net-(IC5-TXD)") (class "Default")
      (node (ref "IC5") (pin "1") (pinfunction "TXD_1") (pintype "bidirectional"))
      (node (ref "IC6") (pin "3") (pinfunction "INB_3") (pintype "bidirectional"))
      (node (ref "R35") (pin "P$1") (pinfunction "1_P$1") (pintype "passive"))
    )
    (net (code "35") (name "Net-(R1-2)") (class "Default")
      (node (ref "LED1") (pin "C") (pinfunction "C_C") (pintype "passive"))
      (node (ref "R1") (pin "P$2") (pinfunction "2_P$2") (pintype "passive"))
    )
    (net (code "36") (name "Net-(R2-2)") (class "Default")
      (node (ref "LED2") (pin "C") (pinfunction "C_C") (pintype "passive"))
      (node (ref "R2") (pin "P$2") (pinfunction "2_P$2") (pintype "passive"))
    )
    (net (code "37") (name "Net-(R3-2)") (class "Default")
      (node (ref "LED3") (pin "C") (pinfunction "C_C") (pintype "passive"))
      (node (ref "R3") (pin "P$2") (pinfunction "2_P$2") (pintype "passive"))
    )
    (net (code "38") (name "Net-(R4-2)") (class "Default")
      (node (ref "LED4") (pin "C") (pinfunction "C_C") (pintype "passive"))
      (node (ref "R4") (pin "P$2") (pinfunction "2_P$2") (pintype "passive"))
    )
    (net (code "39") (name "Net-(R11-2)") (class "Default")
      (node (ref "LED5") (pin "C") (pinfunction "C_C") (pintype "passive"))
      (node (ref "R11") (pin "P$2") (pinfunction "2_P$2") (pintype "passive"))
    )
    (net (code "40") (name "Net-(R21-2)") (class "Default")
      (node (ref "R21") (pin "P$2") (pinfunction "2_P$2") (pintype "passive"))
      (node (ref "X2") (pin "2") (pinfunction "2_2") (pintype "bidirectional"))
    )
    (net (code "41") (name "Net-(R24-2)") (class "Default")
      (node (ref "R24") (pin "P$2") (pinfunction "2_P$2") (pintype "passive"))
      (node (ref "X2") (pin "3") (pinfunction "3_3") (pintype "bidirectional"))
    )
    (net (code "42") (name "PB8") (class "Default")
      (node (ref "IC3") (pin "45") (pinfunction "PB8-TIM4CH3-I2C1SCL/CANRX_45") (pintype "bidirectional"))
      (node (ref "TP20") (pin "P$1") (pinfunction "1_P$1") (pintype "bidirectional"))
    )
    (net (code "43") (name "PB9") (class "Default")
      (node (ref "IC3") (pin "46") (pinfunction "PB9-TIM4CH4-I2C1SDA/CANTX_46") (pintype "bidirectional"))
      (node (ref "TP21") (pin "P$1") (pinfunction "1_P$1") (pintype "bidirectional"))
    )
    (net (code "44") (name "PB10") (class "Default")
      (node (ref "IC3") (pin "21") (pinfunction "PB10-I2C2SCL/USART3TX-TIM2CH3_21") (pintype "bidirectional"))
      (node (ref "TP22") (pin "P$1") (pinfunction "1_P$1") (pintype "bidirectional"))
    )
    (net (code "45") (name "PB11") (class "Default")
      (node (ref "IC3") (pin "22") (pinfunction "PB11-I2C2SDA/USART3RX-TIM2CH4_22") (pintype "bidirectional"))
      (node (ref "TP23") (pin "P$1") (pinfunction "1_P$1") (pintype "bidirectional"))
    )
    (net (code "46") (name "PHASE_U") (class "Default")
      (node (ref "C23") (pin "-") (pinfunction "-_-") (pintype "passive"))
      (node (ref "IC2") (pin "6") (pinfunction "VS_6") (pintype "bidirectional"))
      (node (ref "R14") (pin "P$1") (pinfunction "1_P$1") (pintype "passive"))
      (node (ref "X4") (pin "3") (pinfunction "3_3") (pintype "bidirectional"))
    )
    (net (code "47") (name "PHASE_V") (class "Default")
      (node (ref "C24") (pin "-") (pinfunction "-_-") (pintype "passive"))
      (node (ref "IC9") (pin "6") (pinfunction "VS_6") (pintype "bidirectional"))
      (node (ref "R16") (pin "P$1") (pinfunction "1_P$1") (pintype "passive"))
      (node (ref "X4") (pin "9") (pinfunction "9_9") (pintype "bidirectional"))
    )
    (net (code "48") (name "PHASE_W") (class "Default")
      (node (ref "C25") (pin "-") (pinfunction "-_-") (pintype "passive"))
      (node (ref "IC10") (pin "6") (pinfunction "VS_6") (pintype "bidirectional"))
      (node (ref "R18") (pin "P$1") (pinfunction "1_P$1") (pintype "passive"))
      (node (ref "X4") (pin "8") (pinfunction "8_8") (pintype "bidirectional"))
    )
    (net (code "49") (name "RST") (class "Default")
      (node (ref "C6") (pin "P$2") (pinfunction "2_P$2") (pintype "passive"))
      (node (ref "IC3") (pin "7") (pinfunction "NRST_7") (pintype "bidirectional"))
      (node (ref "JTAG") (pin "10") (pinfunction "10_10") (pintype "bidirectional"))
    )
    (net (code "50") (name "RXD") (class "Default")
      (node (ref "IC3") (pin "43") (pinfunction "PB7-I2C1SDA/TIM4CH2-USART1RX_43") (pintype "bidirectional"))
      (node (ref "R19") (pin "P$2") (pinfunction "2_P$2") (pintype "passive"))
      (node (ref "R21") (pin "P$1") (pinfunction "1_P$1") (pintype "passive"))
    )
    (net (code "51") (name "SHUNT") (class "Default")
      (node (ref "R27") (pin "P$2") (pinfunction "2_P$2") (pintype "passive"))
      (node (ref "X4") (pin "10") (pinfunction "10_10") (pintype "bidirectional"))
    )
    (net (code "52") (name "STAR_VOLTAGE") (class "Default")
      (node (ref "R23") (pin "P$2") (pinfunction "2_P$2") (pintype "passive"))
      (node (ref "R25") (pin "P$2") (pinfunction "2_P$2") (pintype "passive"))
      (node (ref "R26") (pin "P$2") (pinfunction "2_P$2") (pintype "passive"))
      (node (ref "TP9") (pin "P$1") (pinfunction "1_P$1") (pintype "bidirectional"))
      (node (ref "U2") (pin "10") (pinfunction "-IN_10") (pintype "input"))
      (node (ref "U2") (pin "6") (pinfunction "-IN_6") (pintype "input"))
      (node (ref "U2") (pin "8") (pinfunction "-IN_8") (pintype "input"))
    )
    (net (code "53") (name "TCK") (class "Default")
      (node (ref "IC3") (pin "37") (pinfunction "PA14/JTCK/SWCLK_37") (pintype "bidirectional"))
      (node (ref "JTAG") (pin "4") (pinfunction "4_4") (pintype "bidirectional"))
    )
    (net (code "54") (name "TDI") (class "Default")
      (node (ref "IC3") (pin "38") (pinfunction "PA15/JTDI-TIM2CH1ETR/SPI1NSS_38") (pintype "bidirectional"))
      (node (ref "JTAG") (pin "8") (pinfunction "8_8") (pintype "bidirectional"))
    )
    (net (code "55") (name "TDO") (class "Default")
      (node (ref "IC3") (pin "39") (pinfunction "PB3/JTDO--TIM2CH2/TRACESWO/SPI1SCK_39") (pintype "bidirectional"))
      (node (ref "JTAG") (pin "6") (pinfunction "6_6") (pintype "bidirectional"))
    )
    (net (code "56") (name "TEMP") (class "Default")
      (node (ref "IC3") (pin "15") (pinfunction "PA5-SPI1SCK/ADC5_15") (pintype "bidirectional"))
      (node (ref "R32") (pin "P$2") (pinfunction "2_P$2") (pintype "passive"))
      (node (ref "TH1") (pin "P$1") (pinfunction "1_P$1") (pintype "passive"))
      (node (ref "TP17") (pin "P$1") (pinfunction "1_P$1") (pintype "bidirectional"))
    )
    (net (code "57") (name "TMS") (class "Default")
      (node (ref "IC3") (pin "34") (pinfunction "PA13/JTMS/SWDIO_34") (pintype "bidirectional"))
      (node (ref "JTAG") (pin "2") (pinfunction "2_2") (pintype "bidirectional"))
    )
    (net (code "58") (name "TXD") (class "Default")
      (node (ref "IC3") (pin "42") (pinfunction "PB6-I2C1SCL/TIM4CH1-USART1TX_42") (pintype "bidirectional"))
      (node (ref "R24") (pin "P$1") (pinfunction "1_P$1") (pintype "passive"))
    )
    (net (code "59") (name "USART_+5V") (class "Default")
      (node (ref "D2") (pin "A") (pinfunction "A_A") (pintype "passive"))
      (node (ref "X2") (pin "4") (pinfunction "4_4") (pintype "bidirectional"))
    )
    (net (code "60") (name "U_COMM") (class "Default")
      (node (ref "IC3") (pin "10") (pinfunction "PA0-WKUP/USART2CTS/ADC0/TIM2CH1ETR_10") (pintype "bidirectional"))
      (node (ref "TP6") (pin "P$1") (pinfunction "1_P$1") (pintype "bidirectional"))
      (node (ref "U2") (pin "13") (pinfunction "OUT_13") (pintype "output"))
    )
    (net (code "61") (name "U_GATE_HIGH") (class "Default")
      (node (ref "IC2") (pin "7") (pinfunction "HO_7") (pintype "bidirectional"))
      (node (ref "X4") (pin "1") (pinfunction "1_1") (pintype "bidirectional"))
    )
    (net (code "62") (name "U_GATE_LOW") (class "Default")
      (node (ref "IC2") (pin "5") (pinfunction "LO_5") (pintype "bidirectional"))
      (node (ref "X4") (pin "5") (pinfunction "5_5") (pintype "bidirectional"))
    )
    (net (code "63") (name "U_HIGH") (class "Default")
      (node (ref "IC2") (pin "2") (pinfunction "HIN_2") (pintype "bidirectional"))
      (node (ref "R5") (pin "P$1") (pinfunction "1_P$1") (pintype "passive"))
      (node (ref "TP10") (pin "P$1") (pinfunction "1_P$1") (pintype "bidirectional"))
    )
    (net (code "64") (name "U_LOW") (class "Default")
      (node (ref "IC2") (pin "3") (pinfunction "LIN_3") (pintype "bidirectional"))
      (node (ref "R8") (pin "P$2") (pinfunction "2_P$2") (pintype "passive"))
      (node (ref "TP11") (pin "P$1") (pinfunction "1_P$1") (pintype "bidirectional"))
    )
    (net (code "65") (name "U_VOLTAGE") (class "Default")
      (node (ref "C36") (pin "P$1") (pinfunction "1_P$1") (pintype "passive"))
      (node (ref "R14") (pin "P$2") (pinfunction "2_P$2") (pintype "passive"))
      (node (ref "R15") (pin "P$1") (pinfunction "1_P$1") (pintype "passive"))
      (node (ref "R23") (pin "P$1") (pinfunction "1_P$1") (pintype "passive"))
      (node (ref "TP3") (pin "P$1") (pinfunction "1_P$1") (pintype "bidirectional"))
      (node (ref "U2") (pin "11") (pinfunction "+IN_11") (pintype "input"))
    )
    (net (code "66") (name "V_BATT") (class "Default")
      (node (ref "IC3") (pin "13") (pinfunction "PA3-USART2RX/ADC3/TIM2CH4_13") (pintype "bidirectional"))
      (node (ref "R12") (pin "P$1") (pinfunction "1_P$1") (pintype "passive"))
      (node (ref "R13") (pin "P$2") (pinfunction "2_P$2") (pintype "passive"))
    )
    (net (code "67") (name "V_COMM") (class "Default")
      (node (ref "IC3") (pin "11") (pinfunction "PA1-USART2RTS/ADC1/TIM2CH2_11") (pintype "bidirectional"))
      (node (ref "TP7") (pin "P$1") (pinfunction "1_P$1") (pintype "bidirectional"))
      (node (ref "U2") (pin "14") (pinfunction "OUT_14") (pintype "output"))
    )
    (net (code "68") (name "V_GATE_HIGH") (class "Default")
      (node (ref "IC9") (pin "7") (pinfunction "HO_7") (pintype "bidirectional"))
      (node (ref "X4") (pin "7") (pinfunction "7_7") (pintype "bidirectional"))
    )
    (net (code "69") (name "V_GATE_LOW") (class "Default")
      (node (ref "IC9") (pin "5") (pinfunction "LO_5") (pintype "bidirectional"))
      (node (ref "X4") (pin "11") (pinfunction "11_11") (pintype "bidirectional"))
    )
    (net (code "70") (name "V_HIGH") (class "Default")
      (node (ref "IC9") (pin "2") (pinfunction "HIN_2") (pintype "bidirectional"))
      (node (ref "R6") (pin "P$1") (pinfunction "1_P$1") (pintype "passive"))
      (node (ref "TP12") (pin "P$1") (pinfunction "1_P$1") (pintype "bidirectional"))
    )
    (net (code "71") (name "V_LOW") (class "Default")
      (node (ref "IC9") (pin "3") (pinfunction "LIN_3") (pintype "bidirectional"))
      (node (ref "R9") (pin "P$2") (pinfunction "2_P$2") (pintype "passive"))
      (node (ref "TP13") (pin "P$1") (pinfunction "1_P$1") (pintype "bidirectional"))
    )
    (net (code "72") (name "V_VOLTAGE") (class "Default")
      (node (ref "C37") (pin "P$1") (pinfunction "1_P$1") (pintype "passive"))
      (node (ref "R16") (pin "P$2") (pinfunction "2_P$2") (pintype "passive"))
      (node (ref "R17") (pin "P$1") (pinfunction "1_P$1") (pintype "passive"))
      (node (ref "R25") (pin "P$1") (pinfunction "1_P$1") (pintype "passive"))
      (node (ref "TP4") (pin "P$1") (pinfunction "1_P$1") (pintype "bidirectional"))
      (node (ref "U2") (pin "9") (pinfunction "+IN_9") (pintype "input"))
    )
    (net (code "73") (name "W_COMM") (class "Default")
      (node (ref "IC3") (pin "12") (pinfunction "PA2-USART2TX/ADC2/TIM2CH3_12") (pintype "bidirectional"))
      (node (ref "TP8") (pin "P$1") (pinfunction "1_P$1") (pintype "bidirectional"))
      (node (ref "U2") (pin "1") (pinfunction "OUT_1") (pintype "output"))
    )
    (net (code "74") (name "W_GATE_HIGH") (class "Default")
      (node (ref "IC10") (pin "7") (pinfunction "HO_7") (pintype "bidirectional"))
      (node (ref "X4") (pin "13") (pinfunction "13_13") (pintype "bidirectional"))
    )
    (net (code "75") (name "W_GATE_LOW") (class "Default")
      (node (ref "IC10") (pin "5") (pinfunction "LO_5") (pintype "bidirectional"))
      (node (ref "X4") (pin "15") (pinfunction "15_15") (pintype "bidirectional"))
    )
    (net (code "76") (name "W_HIGH") (class "Default")
      (node (ref "IC10") (pin "2") (pinfunction "HIN_2") (pintype "bidirectional"))
      (node (ref "R7") (pin "P$1") (pinfunction "1_P$1") (pintype "passive"))
      (node (ref "TP14") (pin "P$1") (pinfunction "1_P$1") (pintype "bidirectional"))
    )
    (net (code "77") (name "W_LOW") (class "Default")
      (node (ref "IC10") (pin "3") (pinfunction "LIN_3") (pintype "bidirectional"))
      (node (ref "R10") (pin "P$2") (pinfunction "2_P$2") (pintype "passive"))
      (node (ref "TP15") (pin "P$1") (pinfunction "1_P$1") (pintype "bidirectional"))
    )
    (net (code "78") (name "W_VOLTAGE") (class "Default")
      (node (ref "C38") (pin "P$1") (pinfunction "1_P$1") (pintype "passive"))
      (node (ref "R18") (pin "P$2") (pinfunction "2_P$2") (pintype "passive"))
      (node (ref "R22") (pin "P$1") (pinfunction "1_P$1") (pintype "passive"))
      (node (ref "R26") (pin "P$1") (pinfunction "1_P$1") (pintype "passive"))
      (node (ref "TP5") (pin "P$1") (pinfunction "1_P$1") (pintype "bidirectional"))
      (node (ref "U2") (pin "7") (pinfunction "+IN_7") (pintype "input"))
    )
    (net (code "79") (name "unconnected-(IC3-PB2{slash}BOOT1-Pad20)") (class "Default")
      (node (ref "IC3") (pin "20") (pinfunction "PB2/BOOT1_20") (pintype "bidirectional"))
    )
    (net (code "80") (name "unconnected-(IC3-PB12-SPI2NSS{slash}I2C2SMBAI{slash}USART3CK{slash}TIM1BKIN-Pad25)") (class "Default")
      (node (ref "IC3") (pin "25") (pinfunction "PB12-SPI2NSS/I2C2SMBAI/USART3CK/TIM1BKIN_25") (pintype "bidirectional"))
    )
    (net (code "81") (name "unconnected-(IC3-PC13-TAMPER-RTC-Pad2)") (class "Default")
      (node (ref "IC3") (pin "2") (pinfunction "PC13-TAMPER-RTC_2") (pintype "bidirectional"))
    )
    (net (code "82") (name "unconnected-(IC3-PC14-OSC32_IN-Pad3)") (class "Default")
      (node (ref "IC3") (pin "3") (pinfunction "PC14-OSC32_IN_3") (pintype "bidirectional"))
    )
    (net (code "83") (name "unconnected-(IC3-PC15-OSC32_OUT-Pad4)") (class "Default")
      (node (ref "IC3") (pin "4") (pinfunction "PC15-OSC32_OUT_4") (pintype "bidirectional"))
    )
    (net (code "84") (name "unconnected-(IC3-PD1-OSC_OUT-CANTX-Pad6)") (class "Default")
      (node (ref "IC3") (pin "6") (pinfunction "PD1-OSC_OUT-CANTX_6") (pintype "output"))
    )
    (net (code "85") (name "unconnected-(IC5-VREF-Pad5)") (class "Default")
      (node (ref "IC5") (pin "5") (pinfunction "VREF_5") (pintype "bidirectional"))
    )
    (net (code "86") (name "unconnected-(Q1-TRI-Pad1)") (class "Default")
      (node (ref "Q1") (pin "1") (pinfunction "TRI_1") (pintype "output"))
    )
    (net (code "87") (name "unconnected-(U2A-OUT-Pad2)") (class "Default")
      (node (ref "U2") (pin "2") (pinfunction "OUT_2") (pintype "output"))
    )
  )
)
